# ESP_Grow_Main_Rev_A_1_Con.net
KiCad netlist of a schematic drawn in Altium Designer
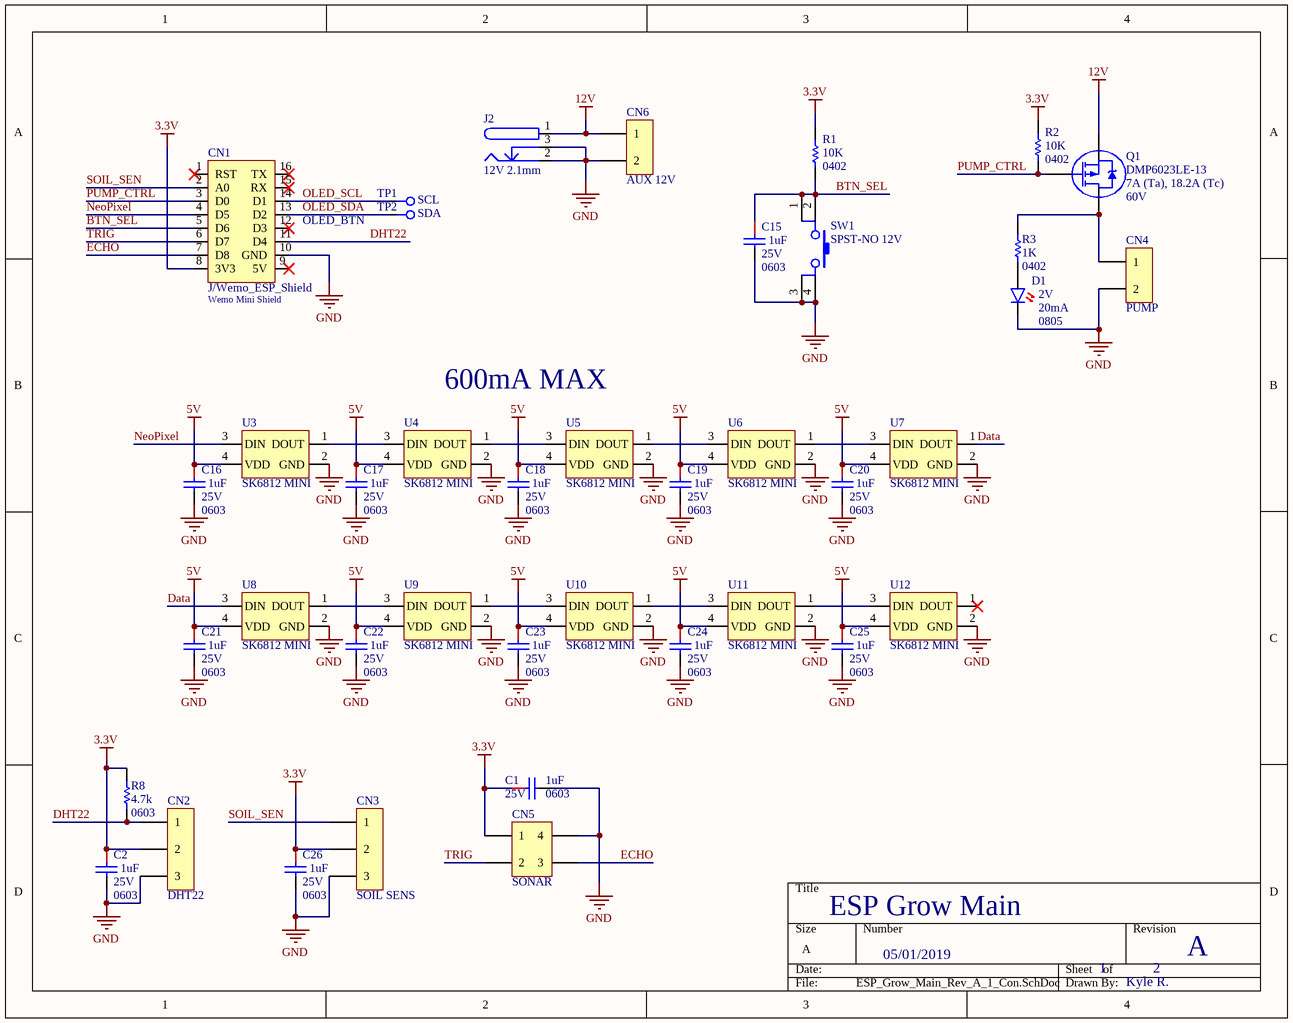
[diagram p0: ESP_Grow_Main_Rev_A_1_Con.SchDoc]

(export (version "E")
  (design (tool "Eeschema 10.0.6"))
  (components
    (comp (ref "C1")
      (value "1uF")
      (footprint "CAPC0603(1608)_N")
      (description "1uF 0603 25V")
      (fields
        (field (name "MANUFACTURER") "TDK Corporation")
        (field (name "MANUFACTURER PART NUMBER") "CGA3E1X7R1E105K080AC")
        (field (name "VOLTAGE - RATED") "25V")
        (field (name "PACKAGE / CASE") "0603")
      )
      (libsource (lib "OLogic-Passive") (part "CAP CER 1UF 25V 10% X7R 0603"))
    )
    (comp (ref "C2")
      (value "1uF")
      (footprint "CAPC0603(1608)_N")
      (description "1uF 0603 25V")
      (fields
        (field (name "MANUFACTURER") "TDK Corporation")
        (field (name "MANUFACTURER PART NUMBER") "CGA3E1X7R1E105K080AC")
        (field (name "VOLTAGE - RATED") "25V")
        (field (name "PACKAGE / CASE") "0603")
      )
      (libsource (lib "OLogic-Passive") (part "CAP CER 1UF 25V 10% X7R 0603"))
    )
    (comp (ref "C15")
      (value "1uF")
      (footprint "CAPC0603(1608)_N")
      (description "1uF 0603 25V")
      (fields
        (field (name "MANUFACTURER") "TDK Corporation")
        (field (name "MANUFACTURER PART NUMBER") "CGA3E1X7R1E105K080AC")
        (field (name "VOLTAGE - RATED") "25V")
        (field (name "PACKAGE / CASE") "0603")
      )
      (libsource (lib "OLogic-Passive") (part "CAP CER 1UF 25V 10% X7R 0603"))
    )
    (comp (ref "C16")
      (value "1uF")
      (footprint "CAPC0603(1608)_N")
      (description "1uF 0603 25V")
      (fields
        (field (name "MANUFACTURER") "TDK Corporation")
        (field (name "MANUFACTURER PART NUMBER") "CGA3E1X7R1E105K080AC")
        (field (name "VOLTAGE - RATED") "25V")
        (field (name "PACKAGE / CASE") "0603")
      )
      (libsource (lib "OLogic-Passive") (part "CAP CER 1UF 25V 10% X7R 0603"))
    )
    (comp (ref "C17")
      (value "1uF")
      (footprint "CAPC0603(1608)_N")
      (description "1uF 0603 25V")
      (fields
        (field (name "MANUFACTURER") "TDK Corporation")
        (field (name "MANUFACTURER PART NUMBER") "CGA3E1X7R1E105K080AC")
        (field (name "VOLTAGE - RATED") "25V")
        (field (name "PACKAGE / CASE") "0603")
      )
      (libsource (lib "OLogic-Passive") (part "CAP CER 1UF 25V 10% X7R 0603"))
    )
    (comp (ref "C18")
      (value "1uF")
      (footprint "CAPC0603(1608)_N")
      (description "1uF 0603 25V")
      (fields
        (field (name "MANUFACTURER") "TDK Corporation")
        (field (name "MANUFACTURER PART NUMBER") "CGA3E1X7R1E105K080AC")
        (field (name "VOLTAGE - RATED") "25V")
        (field (name "PACKAGE / CASE") "0603")
      )
      (libsource (lib "OLogic-Passive") (part "CAP CER 1UF 25V 10% X7R 0603"))
    )
    (comp (ref "C19")
      (value "1uF")
      (footprint "CAPC0603(1608)_N")
      (description "1uF 0603 25V")
      (fields
        (field (name "MANUFACTURER") "TDK Corporation")
        (field (name "MANUFACTURER PART NUMBER") "CGA3E1X7R1E105K080AC")
        (field (name "VOLTAGE - RATED") "25V")
        (field (name "PACKAGE / CASE") "0603")
      )
      (libsource (lib "OLogic-Passive") (part "CAP CER 1UF 25V 10% X7R 0603"))
    )
    (comp (ref "C20")
      (value "1uF")
      (footprint "CAPC0603(1608)_N")
      (description "1uF 0603 25V")
      (fields
        (field (name "MANUFACTURER") "TDK Corporation")
        (field (name "MANUFACTURER PART NUMBER") "CGA3E1X7R1E105K080AC")
        (field (name "VOLTAGE - RATED") "25V")
        (field (name "PACKAGE / CASE") "0603")
      )
      (libsource (lib "OLogic-Passive") (part "CAP CER 1UF 25V 10% X7R 0603"))
    )
    (comp (ref "C21")
      (value "1uF")
      (footprint "CAPC0603(1608)_N")
      (description "1uF 0603 25V")
      (fields
        (field (name "MANUFACTURER") "TDK Corporation")
        (field (name "MANUFACTURER PART NUMBER") "CGA3E1X7R1E105K080AC")
        (field (name "VOLTAGE - RATED") "25V")
        (field (name "PACKAGE / CASE") "0603")
      )
      (libsource (lib "OLogic-Passive") (part "CAP CER 1UF 25V 10% X7R 0603"))
    )
    (comp (ref "C22")
      (value "1uF")
      (footprint "CAPC0603(1608)_N")
      (description "1uF 0603 25V")
      (fields
        (field (name "MANUFACTURER") "TDK Corporation")
        (field (name "MANUFACTURER PART NUMBER") "CGA3E1X7R1E105K080AC")
        (field (name "VOLTAGE - RATED") "25V")
        (field (name "PACKAGE / CASE") "0603")
      )
      (libsource (lib "OLogic-Passive") (part "CAP CER 1UF 25V 10% X7R 0603"))
    )
    (comp (ref "C23")
      (value "1uF")
      (footprint "CAPC0603(1608)_N")
      (description "1uF 0603 25V")
      (fields
        (field (name "MANUFACTURER") "TDK Corporation")
        (field (name "MANUFACTURER PART NUMBER") "CGA3E1X7R1E105K080AC")
        (field (name "VOLTAGE - RATED") "25V")
        (field (name "PACKAGE / CASE") "0603")
      )
      (libsource (lib "OLogic-Passive") (part "CAP CER 1UF 25V 10% X7R 0603"))
    )
    (comp (ref "C24")
      (value "1uF")
      (footprint "CAPC0603(1608)_N")
      (description "1uF 0603 25V")
      (fields
        (field (name "MANUFACTURER") "TDK Corporation")
        (field (name "MANUFACTURER PART NUMBER") "CGA3E1X7R1E105K080AC")
        (field (name "VOLTAGE - RATED") "25V")
        (field (name "PACKAGE / CASE") "0603")
      )
      (libsource (lib "OLogic-Passive") (part "CAP CER 1UF 25V 10% X7R 0603"))
    )
    (comp (ref "C25")
      (value "1uF")
      (footprint "CAPC0603(1608)_N")
      (description "1uF 0603 25V")
      (fields
        (field (name "MANUFACTURER") "TDK Corporation")
        (field (name "MANUFACTURER PART NUMBER") "CGA3E1X7R1E105K080AC")
        (field (name "VOLTAGE - RATED") "25V")
        (field (name "PACKAGE / CASE") "0603")
      )
      (libsource (lib "OLogic-Passive") (part "CAP CER 1UF 25V 10% X7R 0603"))
    )
    (comp (ref "C26")
      (value "1uF")
      (footprint "CAPC0603(1608)_N")
      (description "1uF 0603 25V")
      (fields
        (field (name "MANUFACTURER") "TDK Corporation")
        (field (name "MANUFACTURER PART NUMBER") "CGA3E1X7R1E105K080AC")
        (field (name "VOLTAGE - RATED") "25V")
        (field (name "PACKAGE / CASE") "0603")
      )
      (libsource (lib "OLogic-Passive") (part "CAP CER 1UF 25V 10% X7R 0603"))
    )
    (comp (ref "CN1")
      (value "J/Wemo_ESP_Shield")
      (footprint "Wemos_d1")
      (description "Wemo Mini Shield for ESP-12")
      (fields (field (name "NAME") "Wemo Mini Shield"))
      (libsource (lib "Kyle_Lib_04-20-19") (part "J/Wemo_ESP_Shield"))
    )
    (comp (ref "CN2")
      (value "DHT22")
      (footprint "Molex 1x3 Microfit 90deg")
      (description "Molex Microfit 1x3 90deg Header")
      (fields
        (field (name "MANUFACTURER") "Molex Inc")
        (field (name "MANUFACTURER PART NUMBER") "0436500304")
      )
      (libsource (lib "OLogic-Connectors") (part "MICROFIT 3.0 HDR 90deg 3CKT"))
    )
    (comp (ref "CN3")
      (value "SOIL SENS")
      (footprint "Molex 1x3 Microfit 90deg")
      (description "Molex Microfit 1x3 90deg Header")
      (fields
        (field (name "MANUFACTURER") "Molex Inc")
        (field (name "MANUFACTURER PART NUMBER") "0436500304")
      )
      (libsource (lib "OLogic-Connectors") (part "MICROFIT 3.0 HDR 90deg 3CKT"))
    )
    (comp (ref "CN4")
      (value "PUMP")
      (footprint "Molex 1x2 Microfit 3.0")
      (description "Molex Microfit 1x2 Vert Header")
      (fields
        (field (name "MANUFACTURER") "Molex, LLC")
        (field (name "MANUFACTURER PART NUMBER") "0430450227")
      )
      (libsource (lib "OLogic-Connectors") (part "MICROFIT 3.0 HDR VERT CPI 2CKT"))
    )
    (comp (ref "CN5")
      (value "SONAR")
      (footprint "Molex 2x2 Microfit 90deg")
      (description "Molex Microfit 2x2 90deg Header")
      (fields
        (field (name "MANUFACTURER") "Molex Inc")
        (field (name "MANUFACTURER PART NUMBER") "0430450400")
      )
      (libsource (lib "OLogic-Connectors") (part "MICROFIT 3.0 HDR 90deg 4CKT"))
    )
    (comp (ref "CN6")
      (value "AUX 12V")
      (footprint "Molex 1x2 Microfit 3.0")
      (description "Molex Microfit 1x2 Vert Header")
      (fields
        (field (name "MANUFACTURER") "Molex, LLC")
        (field (name "MANUFACTURER PART NUMBER") "0430450227")
      )
      (libsource (lib "OLogic-Connectors") (part "MICROFIT 3.0 HDR VERT CPI 2CKT"))
    )
    (comp (ref "D1")
      (value "D/LEDR/0805")
      (footprint "D/0805")
      (description "Red 625nm LED Indication - Discrete 2V 0805")
      (fields
        (field (name "DIGIKEY PART") "732-4984-1-ND")
        (field (name "VOLTAGE - FORWARD (VF) (TYP)") "2V")
        (field (name "CURRENT - TEST") "20mA")
        (field (name "PACKAGE / CASE") "0805")
      )
      (libsource (lib "Kyle_Lib_04-20-19") (part "D/LEDR/0805"))
    )
    (comp (ref "J2")
      (value "12V 2.1mm")
      (footprint "CONN_PWR_JACK_2.1x5.5mm")
      (description "2.1 mm barrel jack")
      (fields
        (field (name "MANUFACTURER") "CUI Inc")
        (field (name "MANUFACTURER PART NUMBER") "PJ-002A")
        (field (name "PUBLISHER") "Altium Limited")
      )
      (libsource (lib "OLogic-Connectors") (part "CONN PWR JACK 2.1"))
    )
    (comp (ref "Q1")
      (value "DMP6023LE-13")
      (footprint "SOT-223 - DMP6023LE")
      (description "MOSFET P-CH 60V 7A SOT223")
      (fields
        (field (name "MANUFACTURER") "Diodes Incorporated")
        (field (name "CURRENT - CONTINUOUS DRAIN (ID) @ 25°C") "7A (Ta), 18.2A (Tc)")
        (field (name "DRAIN TO SOURCE VOLTAGE (VDSS)") "60V")
      )
      (libsource (lib "OLogic-Trans-Drivers") (part "DMP6023LE-13"))
    )
    (comp (ref "R1")
      (value "10K")
      (footprint "RESC0402(1005)_N")
      (description "10K 0402")
      (fields
        (field (name "MANUFACTURER") "Samsung Electro-Mechanics")
        (field (name "MANUFACTURER PART NUMBER") "RC1005F103CS")
        (field (name "SUPPLIER DEVICE PACKAGE") "0402")
      )
      (libsource (lib "OLogic-Passive") (part "RES 10K OHM 1% 1/16W 0402"))
    )
    (comp (ref "R2")
      (value "10K")
      (footprint "RESC0402(1005)_N")
      (description "10K 0402")
      (fields
        (field (name "MANUFACTURER") "Samsung Electro-Mechanics")
        (field (name "MANUFACTURER PART NUMBER") "RC1005F103CS")
        (field (name "SUPPLIER DEVICE PACKAGE") "0402")
      )
      (libsource (lib "OLogic-Passive") (part "RES 10K OHM 1% 1/16W 0402"))
    )
    (comp (ref "R3")
      (value "1K")
      (footprint "RESC0402(1005)_L")
      (description "1K 0402")
      (fields
        (field (name "MANUFACTURER") "Yageo")
        (field (name "MANUFACTURER PART NUMBER") "RC0402FR-071KL")
        (field (name "RESISTANCE") "1K")
        (field (name "PACKAGE / CASE") "0402")
      )
      (libsource (lib "OLogic-Passive") (part "RES 1K OHM 1% 1/16W 0402"))
    )
    (comp (ref "R8")
      (value "4.7K")
      (footprint "RESC0603(1608)_N")
      (description "4.7K 0603")
      (fields
        (field (name "MANUFACTURER") "Panasonic Electronic Components")
        (field (name "MANUFACTURER PART NUMBER") "ERJ-3GEYJ472V")
        (field (name "RESISTANCE (OHMS)") "4.7k")
        (field (name "PACKAGE / CASE") "0603")
      )
      (libsource (lib "OLogic-Passive") (part "RES 4.7K OHM 1/10W 5% 0603 SMD"))
    )
    (comp (ref "SW1")
      (value "SPST-NO 12V")
      (footprint "SW TACT Red 6mm x 6mm")
      (description "SWITCH TACTILE SPST-NO 0.05A 12V")
      (fields
        (field (name "MANUFACTURER") "C&K")
        (field (name "MANUFACTURER PART NUMBER") "PTS645SM43SMTR92 LFS")
      )
      (libsource (lib "OLogic-Switches") (part "PTS645SM43SMTR92 LFS"))
    )
    (comp (ref "TP1")
      (value "SCL")
      (footprint "Pogo-Testpoint")
      (description "Test Point- Current one")
      (libsource (lib "OLogic Nexus Vault") (part "TestPoint"))
    )
    (comp (ref "TP2")
      (value "SDA")
      (footprint "Pogo-Testpoint")
      (description "Test Point- Current one")
      (libsource (lib "OLogic Nexus Vault") (part "TestPoint"))
    )
    (comp (ref "U3")
      (value "SK6812 MINI")
      (footprint "SK6812_Mini")
      (description "Serial RGB LED SMT5050")
      (libsource (lib "Kyle_Lib_04-20-19") (part "U/SK6812MINI"))
    )
    (comp (ref "U4")
      (value "SK6812 MINI")
      (footprint "SK6812_Mini")
      (description "Serial RGB LED SMT5050")
      (libsource (lib "Kyle_Lib_04-20-19") (part "U/SK6812MINI"))
    )
    (comp (ref "U5")
      (value "SK6812 MINI")
      (footprint "SK6812_Mini")
      (description "Serial RGB LED SMT5050")
      (libsource (lib "Kyle_Lib_04-20-19") (part "U/SK6812MINI"))
    )
    (comp (ref "U6")
      (value "SK6812 MINI")
      (footprint "SK6812_Mini")
      (description "Serial RGB LED SMT5050")
      (libsource (lib "Kyle_Lib_04-20-19") (part "U/SK6812MINI"))
    )
    (comp (ref "U7")
      (value "SK6812 MINI")
      (footprint "SK6812_Mini")
      (description "Serial RGB LED SMT5050")
      (libsource (lib "Kyle_Lib_04-20-19") (part "U/SK6812MINI"))
    )
    (comp (ref "U8")
      (value "SK6812 MINI")
      (footprint "SK6812_Mini")
      (description "Serial RGB LED SMT5050")
      (libsource (lib "Kyle_Lib_04-20-19") (part "U/SK6812MINI"))
    )
    (comp (ref "U9")
      (value "SK6812 MINI")
      (footprint "SK6812_Mini")
      (description "Serial RGB LED SMT5050")
      (libsource (lib "Kyle_Lib_04-20-19") (part "U/SK6812MINI"))
    )
    (comp (ref "U10")
      (value "SK6812 MINI")
      (footprint "SK6812_Mini")
      (description "Serial RGB LED SMT5050")
      (libsource (lib "Kyle_Lib_04-20-19") (part "U/SK6812MINI"))
    )
    (comp (ref "U11")
      (value "SK6812 MINI")
      (footprint "SK6812_Mini")
      (description "Serial RGB LED SMT5050")
      (libsource (lib "Kyle_Lib_04-20-19") (part "U/SK6812MINI"))
    )
    (comp (ref "U12")
      (value "SK6812 MINI")
      (footprint "SK6812_Mini")
      (description "Serial RGB LED SMT5050")
      (libsource (lib "Kyle_Lib_04-20-19") (part "U/SK6812MINI"))
    )
  )
  (nets
    (net (code "1") (name "/BTN_SEL") (class "Default")
      (node (ref "C15") (pin "1") (pinfunction "1_1") (pintype "passive"))
      (node (ref "CN1") (pin "5") (pinfunction "D6_5") (pintype "power_in"))
      (node (ref "R1") (pin "1") (pinfunction "1_1") (pintype "passive"))
      (node (ref "SW1") (pin "1") (pinfunction "1_1") (pintype "passive"))
      (node (ref "SW1") (pin "2") (pinfunction "2_2") (pintype "passive"))
    )
    (net (code "2") (name "/DHT22") (class "Default")
      (node (ref "CN1") (pin "11") (pinfunction "D4_11") (pintype "power_in"))
      (node (ref "CN2") (pin "1") (pinfunction "1_1") (pintype "passive"))
      (node (ref "R8") (pin "1") (pinfunction "1_1") (pintype "passive"))
    )
    (net (code "3") (name "/Data") (class "Default")
      (node (ref "U7") (pin "1") (pinfunction "DOUT_1") (pintype "power_in"))
      (node (ref "U8") (pin "3") (pinfunction "DIN_3") (pintype "power_in"))
    )
    (net (code "4") (name "/ECHO") (class "Default")
      (node (ref "CN1") (pin "7") (pinfunction "D8_7") (pintype "power_in"))
      (node (ref "CN5") (pin "3") (pinfunction "3_3") (pintype "passive"))
    )
    (net (code "5") (name "/NeoPixel") (class "Default")
      (node (ref "CN1") (pin "4") (pinfunction "D5_4") (pintype "power_in"))
      (node (ref "U3") (pin "3") (pinfunction "DIN_3") (pintype "power_in"))
    )
    (net (code "6") (name "/OLED_SCL") (class "Default")
      (node (ref "CN1") (pin "14") (pinfunction "D1_14") (pintype "power_in"))
      (node (ref "TP1") (pin "1") (pinfunction "1_1") (pintype "passive"))
    )
    (net (code "7") (name "/OLED_SDA") (class "Default")
      (node (ref "CN1") (pin "13") (pinfunction "D2_13") (pintype "power_in"))
      (node (ref "TP2") (pin "1") (pinfunction "1_1") (pintype "passive"))
    )
    (net (code "8") (name "/PUMP_CTRL") (class "Default")
      (node (ref "CN1") (pin "3") (pinfunction "D0_3") (pintype "power_in"))
      (node (ref "Q1") (pin "G") (pinfunction "G_G") (pintype "passive"))
      (node (ref "R2") (pin "1") (pinfunction "1_1") (pintype "passive"))
    )
    (net (code "9") (name "/SOIL_SEN") (class "Default")
      (node (ref "CN1") (pin "2") (pinfunction "A0_2") (pintype "power_in"))
      (node (ref "CN3") (pin "1") (pinfunction "1_1") (pintype "passive"))
    )
    (net (code "10") (name "/TRIG") (class "Default")
      (node (ref "CN1") (pin "6") (pinfunction "D7_6") (pintype "power_in"))
      (node (ref "CN5") (pin "2") (pinfunction "2_2") (pintype "passive"))
    )
    (net (code "11") (name "3.3V") (class "Default")
      (node (ref "C1") (pin "1") (pinfunction "1_1") (pintype "passive"))
      (node (ref "C2") (pin "1") (pinfunction "1_1") (pintype "passive"))
      (node (ref "C26") (pin "1") (pinfunction "1_1") (pintype "passive"))
      (node (ref "CN1") (pin "8") (pinfunction "3V3_8") (pintype "power_in"))
      (node (ref "CN2") (pin "2") (pinfunction "2_2") (pintype "passive"))
      (node (ref "CN3") (pin "2") (pinfunction "2_2") (pintype "passive"))
      (node (ref "CN5") (pin "1") (pinfunction "1_1") (pintype "passive"))
      (node (ref "R1") (pin "2") (pinfunction "2_2") (pintype "passive"))
      (node (ref "R2") (pin "2") (pinfunction "2_2") (pintype "passive"))
      (node (ref "R8") (pin "2") (pinfunction "2_2") (pintype "passive"))
    )
    (net (code "12") (name "5V") (class "Default")
      (node (ref "C16") (pin "1") (pinfunction "1_1") (pintype "passive"))
      (node (ref "C17") (pin "1") (pinfunction "1_1") (pintype "passive"))
      (node (ref "C18") (pin "1") (pinfunction "1_1") (pintype "passive"))
      (node (ref "C19") (pin "1") (pinfunction "1_1") (pintype "passive"))
      (node (ref "C20") (pin "1") (pinfunction "1_1") (pintype "passive"))
      (node (ref "C21") (pin "1") (pinfunction "1_1") (pintype "passive"))
      (node (ref "C22") (pin "1") (pinfunction "1_1") (pintype "passive"))
      (node (ref "C23") (pin "1") (pinfunction "1_1") (pintype "passive"))
      (node (ref "C24") (pin "1") (pinfunction "1_1") (pintype "passive"))
      (node (ref "C25") (pin "1") (pinfunction "1_1") (pintype "passive"))
      (node (ref "U10") (pin "4") (pinfunction "VDD_4") (pintype "power_in"))
      (node (ref "U11") (pin "4") (pinfunction "VDD_4") (pintype "power_in"))
      (node (ref "U12") (pin "4") (pinfunction "VDD_4") (pintype "power_in"))
      (node (ref "U3") (pin "4") (pinfunction "VDD_4") (pintype "power_in"))
      (node (ref "U4") (pin "4") (pinfunction "VDD_4") (pintype "power_in"))
      (node (ref "U5") (pin "4") (pinfunction "VDD_4") (pintype "power_in"))
      (node (ref "U6") (pin "4") (pinfunction "VDD_4") (pintype "power_in"))
      (node (ref "U7") (pin "4") (pinfunction "VDD_4") (pintype "power_in"))
      (node (ref "U8") (pin "4") (pinfunction "VDD_4") (pintype "power_in"))
      (node (ref "U9") (pin "4") (pinfunction "VDD_4") (pintype "power_in"))
    )
    (net (code "13") (name "12V") (class "Default")
      (node (ref "CN6") (pin "1") (pinfunction "1_1") (pintype "passive"))
      (node (ref "J2") (pin "1") (pinfunction "1_1") (pintype "power_in"))
      (node (ref "Q1") (pin "S") (pinfunction "S_S") (pintype "passive"))
    )
    (net (code "14") (name "GND") (class "Default")
      (node (ref "C1") (pin "2") (pinfunction "2_2") (pintype "passive"))
      (node (ref "C15") (pin "2") (pinfunction "2_2") (pintype "passive"))
      (node (ref "C16") (pin "2") (pinfunction "2_2") (pintype "passive"))
      (node (ref "C17") (pin "2") (pinfunction "2_2") (pintype "passive"))
      (node (ref "C18") (pin "2") (pinfunction "2_2") (pintype "passive"))
      (node (ref "C19") (pin "2") (pinfunction "2_2") (pintype "passive"))
      (node (ref "C2") (pin "2") (pinfunction "2_2") (pintype "passive"))
      (node (ref "C20") (pin "2") (pinfunction "2_2") (pintype "passive"))
      (node (ref "C21") (pin "2") (pinfunction "2_2") (pintype "passive"))
      (node (ref "C22") (pin "2") (pinfunction "2_2") (pintype "passive"))
      (node (ref "C23") (pin "2") (pinfunction "2_2") (pintype "passive"))
      (node (ref "C24") (pin "2") (pinfunction "2_2") (pintype "passive"))
      (node (ref "C25") (pin "2") (pinfunction "2_2") (pintype "passive"))
      (node (ref "C26") (pin "2") (pinfunction "2_2") (pintype "passive"))
      (node (ref "CN1") (pin "10") (pinfunction "GND_10") (pintype "power_in"))
      (node (ref "CN2") (pin "3") (pinfunction "3_3") (pintype "passive"))
      (node (ref "CN3") (pin "3") (pinfunction "3_3") (pintype "passive"))
      (node (ref "CN4") (pin "2") (pinfunction "2_2") (pintype "passive"))
      (node (ref "CN5") (pin "4") (pinfunction "4_4") (pintype "passive"))
      (node (ref "CN6") (pin "2") (pinfunction "2_2") (pintype "passive"))
      (node (ref "D1") (pin "1") (pinfunction "1_1") (pintype "passive"))
      (node (ref "J2") (pin "2") (pinfunction "2_2") (pintype "power_in"))
      (node (ref "J2") (pin "3") (pinfunction "3_3") (pintype "power_in"))
      (node (ref "SW1") (pin "3") (pinfunction "3_3") (pintype "passive"))
      (node (ref "SW1") (pin "4") (pinfunction "4_4") (pintype "passive"))
      (node (ref "U10") (pin "2") (pinfunction "GND_2") (pintype "power_in"))
      (node (ref "U11") (pin "2") (pinfunction "GND_2") (pintype "power_in"))
      (node (ref "U12") (pin "2") (pinfunction "GND_2") (pintype "power_in"))
      (node (ref "U3") (pin "2") (pinfunction "GND_2") (pintype "power_in"))
      (node (ref "U4") (pin "2") (pinfunction "GND_2") (pintype "power_in"))
      (node (ref "U5") (pin "2") (pinfunction "GND_2") (pintype "power_in"))
      (node (ref "U6") (pin "2") (pinfunction "GND_2") (pintype "power_in"))
      (node (ref "U7") (pin "2") (pinfunction "GND_2") (pintype "power_in"))
      (node (ref "U8") (pin "2") (pinfunction "GND_2") (pintype "power_in"))
      (node (ref "U9") (pin "2") (pinfunction "GND_2") (pintype "power_in"))
    )
    (net (code "15") (name "Net-(CN4-Pad1)") (class "Default")
      (node (ref "CN4") (pin "1") (pinfunction "1_1") (pintype "passive"))
      (node (ref "Q1") (pin "D") (pinfunction "D_D") (pintype "passive"))
      (node (ref "R3") (pin "2") (pinfunction "2_2") (pintype "passive"))
    )
    (net (code "16") (name "Net-(D1-Pad2)") (class "Default")
      (node (ref "D1") (pin "2") (pinfunction "2_2") (pintype "passive"))
      (node (ref "R3") (pin "1") (pinfunction "1_1") (pintype "passive"))
    )
    (net (code "17") (name "Net-(U3-DOUT)") (class "Default")
      (node (ref "U3") (pin "1") (pinfunction "DOUT_1") (pintype "power_in"))
      (node (ref "U4") (pin "3") (pinfunction "DIN_3") (pintype "power_in"))
    )
    (net (code "18") (name "Net-(U4-DOUT)") (class "Default")
      (node (ref "U4") (pin "1") (pinfunction "DOUT_1") (pintype "power_in"))
      (node (ref "U5") (pin "3") (pinfunction "DIN_3") (pintype "power_in"))
    )
    (net (code "19") (name "Net-(U5-DOUT)") (class "Default")
      (node (ref "U5") (pin "1") (pinfunction "DOUT_1") (pintype "power_in"))
      (node (ref "U6") (pin "3") (pinfunction "DIN_3") (pintype "power_in"))
    )
    (net (code "20") (name "Net-(U6-DOUT)") (class "Default")
      (node (ref "U6") (pin "1") (pinfunction "DOUT_1") (pintype "power_in"))
      (node (ref "U7") (pin "3") (pinfunction "DIN_3") (pintype "power_in"))
    )
    (net (code "21") (name "Net-(U8-DOUT)") (class "Default")
      (node (ref "U8") (pin "1") (pinfunction "DOUT_1") (pintype "power_in"))
      (node (ref "U9") (pin "3") (pinfunction "DIN_3") (pintype "power_in"))
    )
    (net (code "22") (name "Net-(U10-DIN)") (class "Default")
      (node (ref "U10") (pin "3") (pinfunction "DIN_3") (pintype "power_in"))
      (node (ref "U9") (pin "1") (pinfunction "DOUT_1") (pintype "power_in"))
    )
    (net (code "23") (name "Net-(U10-DOUT)") (class "Default")
      (node (ref "U10") (pin "1") (pinfunction "DOUT_1") (pintype "power_in"))
      (node (ref "U11") (pin "3") (pinfunction "DIN_3") (pintype "power_in"))
    )
    (net (code "24") (name "Net-(U11-DOUT)") (class "Default")
      (node (ref "U11") (pin "1") (pinfunction "DOUT_1") (pintype "power_in"))
      (node (ref "U12") (pin "3") (pinfunction "DIN_3") (pintype "power_in"))
    )
    (net (code "25") (name "unconnected-(CN1-5V-Pad9)") (class "Default")
      (node (ref "CN1") (pin "9") (pinfunction "5V_9") (pintype "power_in+no_connect"))
    )
    (net (code "26") (name "unconnected-(CN1-D3-Pad12)") (class "Default")
      (node (ref "CN1") (pin "12") (pinfunction "D3_12") (pintype "power_in+no_connect"))
    )
    (net (code "27") (name "unconnected-(CN1-RST-Pad1)") (class "Default")
      (node (ref "CN1") (pin "1") (pinfunction "RST_1") (pintype "power_in+no_connect"))
    )
    (net (code "28") (name "unconnected-(CN1-RX-Pad15)") (class "Default")
      (node (ref "CN1") (pin "15") (pinfunction "RX_15") (pintype "power_in+no_connect"))
    )
    (net (code "29") (name "unconnected-(CN1-TX-Pad16)") (class "Default")
      (node (ref "CN1") (pin "16") (pinfunction "TX_16") (pintype "power_in+no_connect"))
    )
    (net (code "30") (name "unconnected-(U12-DOUT-Pad1)") (class "Default")
      (node (ref "U12") (pin "1") (pinfunction "DOUT_1") (pintype "power_in+no_connect"))
    )
  )
)
